# PROC010B_CAN_Interface.net
KiCad netlist of a schematic drawn in Altium Designer
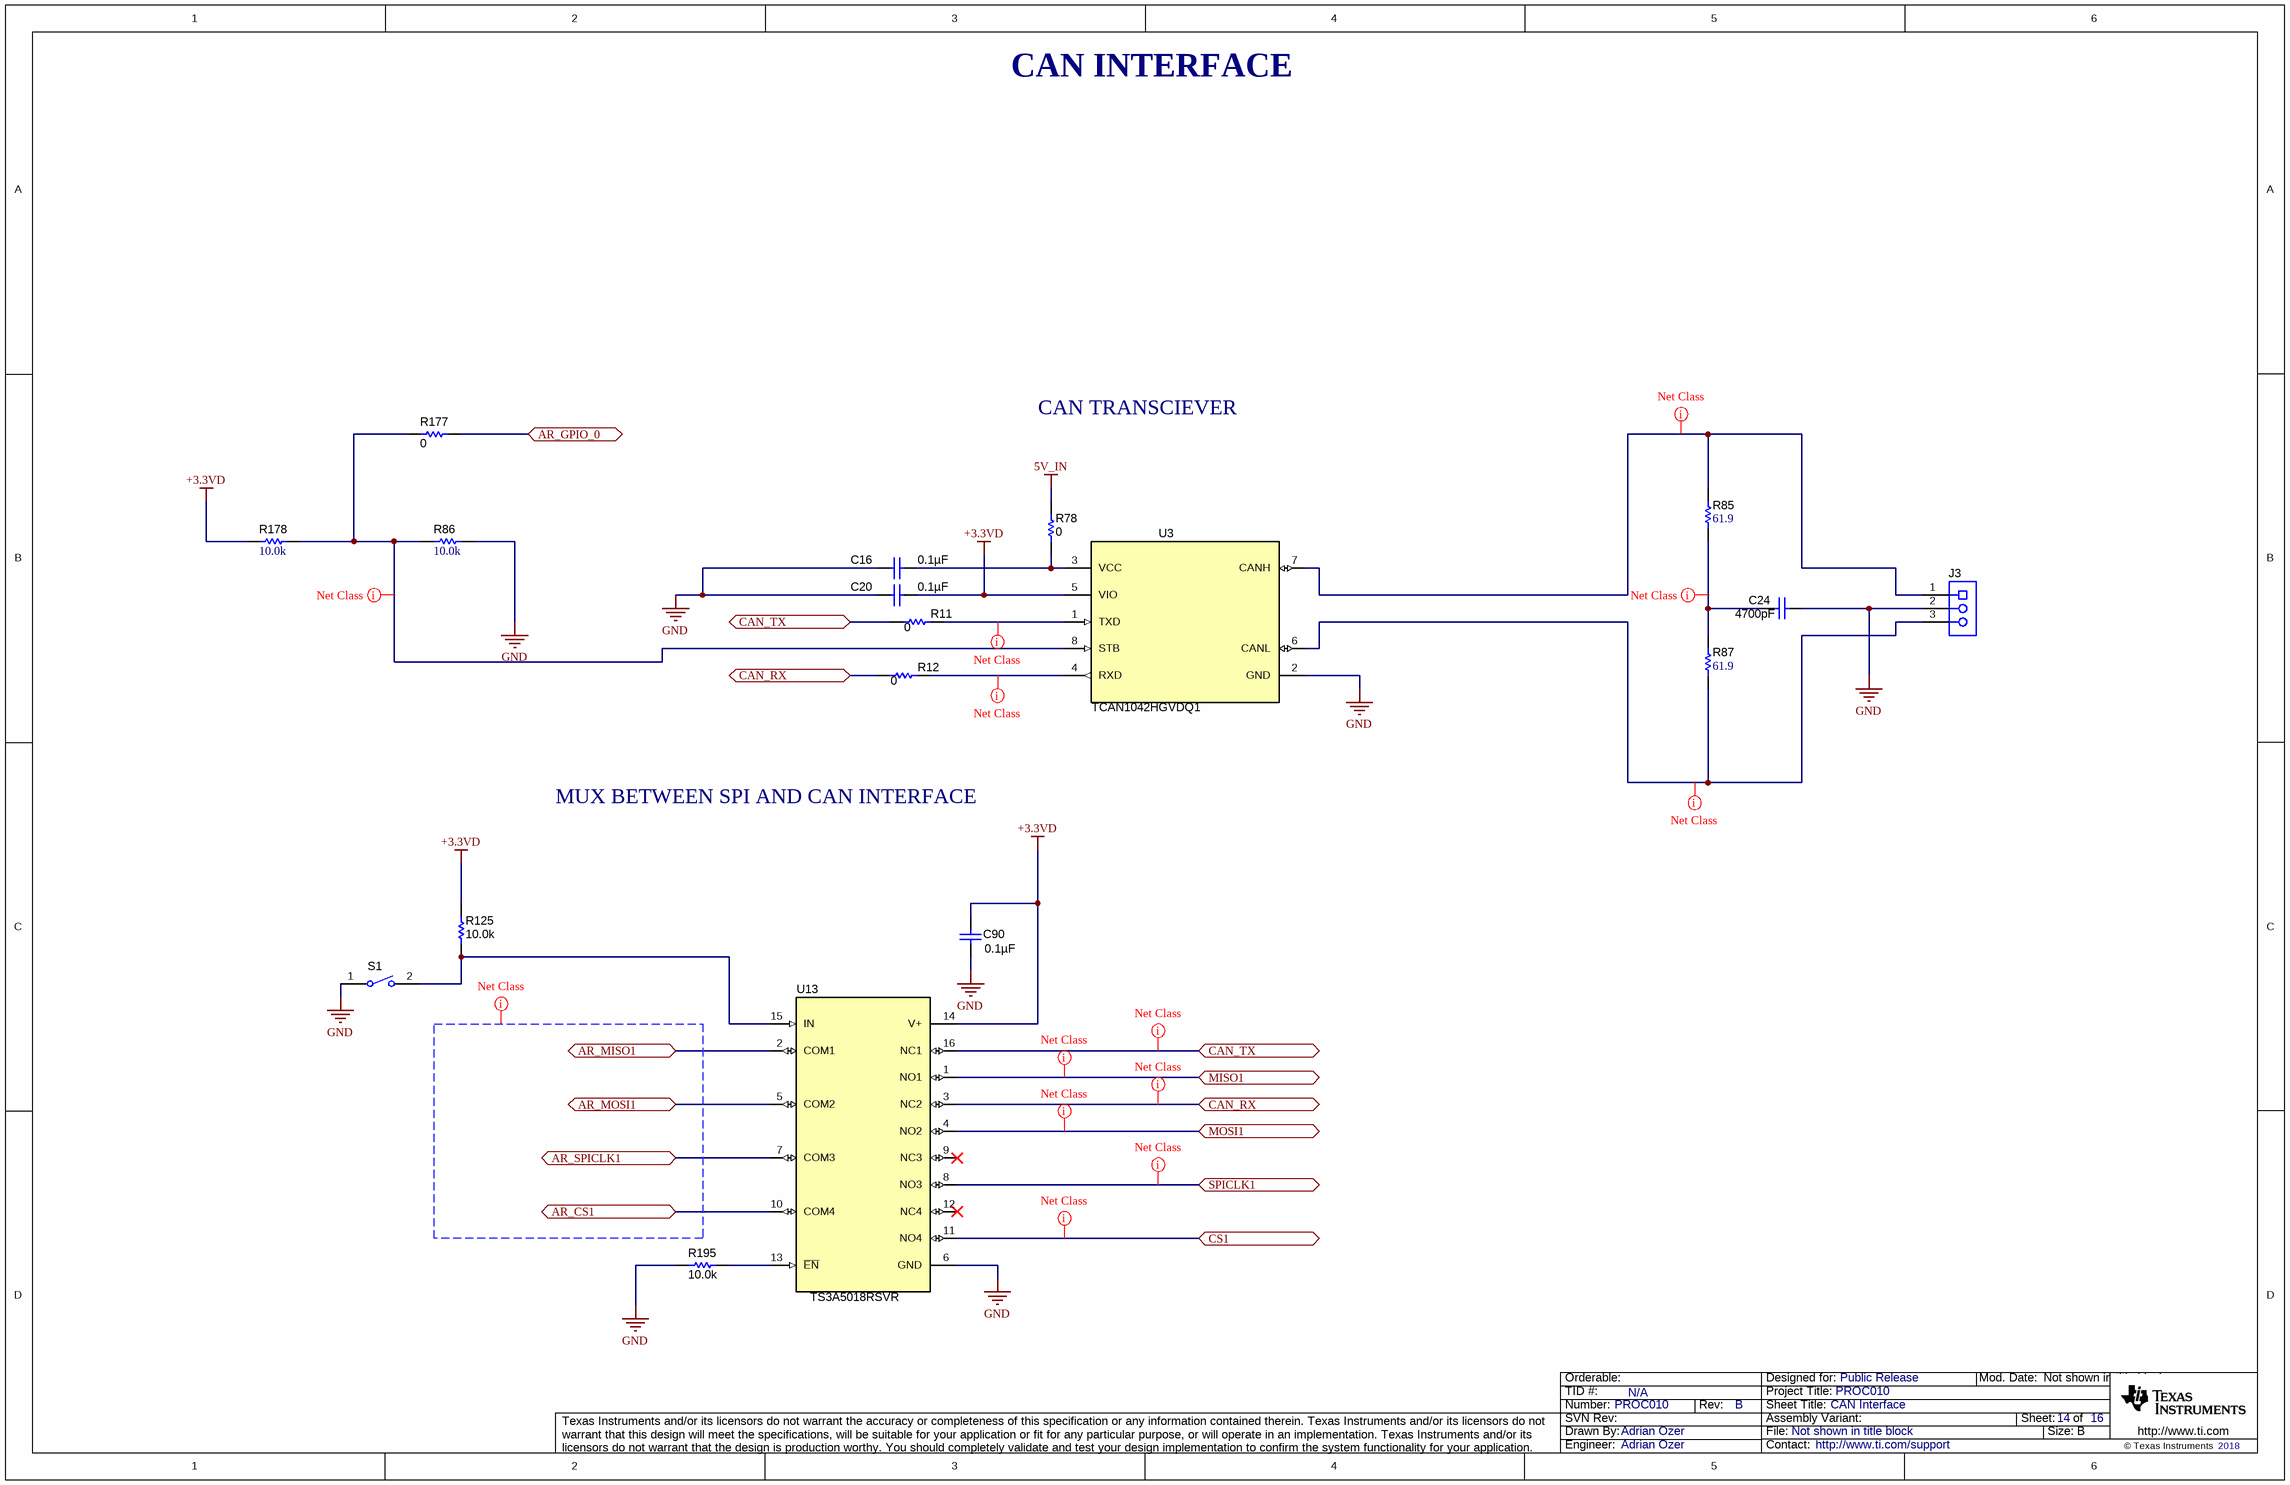
[diagram p0: PROC010B_CAN Interface.SchDoc]

(export (version "E")
  (design (tool "Eeschema 10.0.6"))
  (components
    (comp (ref "C16")
      (value "C0402C104K8RACTU")
      (footprint "0402L")
      (description "CAP, CERM, 0.1 µF, 10 V,+/- 10%, X7R, 0402")
      (fields (field (name "MANUFACTURER") "Kemet") (field (name "VALUEDISPLAYED") "0.1µF"))
      (libsource (lib "Altium Vault - TI") (part "Capacitor"))
    )
    (comp (ref "C20")
      (value "C0402C104K8RACTU")
      (footprint "0402L")
      (description "CAP, CERM, 0.1 µF, 10 V,+/- 10%, X7R, 0402")
      (fields (field (name "MANUFACTURER") "Kemet") (field (name "VALUEDISPLAYED") "0.1µF"))
      (libsource (lib "Altium Vault - TI") (part "Capacitor"))
    )
    (comp (ref "C24")
      (value "C1005X7R1H472K050BA")
      (footprint "0402L")
      (description "CAP, CERM, 4700 pF, 50 V,+/- 10%, X7R, 0402")
      (fields (field (name "MANUFACTURER") "TDK") (field (name "VALUEDISPLAYED") "4700pF"))
      (libsource (lib "Altium Vault - TI") (part "Capacitor"))
    )
    (comp (ref "C90")
      (value "C0402C104K8RACTU")
      (footprint "0402L")
      (description "CAP, CERM, 0.1 µF, 10 V,+/- 10%, X7R, 0402")
      (fields (field (name "MANUFACTURER") "Kemet") (field (name "VALUEDISPLAYED") "0.1µF"))
      (libsource (lib "Altium Vault - TI") (part "Capacitor"))
    )
    (comp (ref "J3")
      (value "OSTTE030161")
      (footprint "On-Shore_OSTTE030161")
      (description "Terminal Block, 3.5mm, 3x1, Tin, R/A, TH")
      (fields
        (field (name "MANUFACTURER") "On-Shore Technology")
        (field (name "PUBLISHER") "Texas Instruments")
      )
      (libsource (lib "Altium Vault - TI") (part "Receptacle_3x1"))
    )
    (comp (ref "R11")
      (value "ERJ-2GE0R00X")
      (footprint "0402L")
      (description "RES, 0, 5%, 0.063 W, 0402")
      (fields
        (field (name "MANUFACTURER") "Panasonic")
        (field (name "VALUEDISPLAYED") "0")
        (field (name "PUBLISHER") "Texas Instruments")
      )
      (libsource (lib "Altium Vault - TI") (part "CMP-0026992-2"))
    )
    (comp (ref "R12")
      (value "ERJ-2GE0R00X")
      (footprint "0402L")
      (description "RES, 0, 5%, 0.063 W, 0402")
      (fields
        (field (name "MANUFACTURER") "Panasonic")
        (field (name "VALUEDISPLAYED") "0")
        (field (name "PUBLISHER") "Texas Instruments")
      )
      (libsource (lib "Altium Vault - TI") (part "CMP-0026992-2"))
    )
    (comp (ref "R78")
      (value "ERJ-2GE0R00X")
      (footprint "0402L")
      (description "RES, 0, 5%, 0.063 W, 0402")
      (fields
        (field (name "MANUFACTURER") "Panasonic")
        (field (name "VALUEDISPLAYED") "0")
        (field (name "PUBLISHER") "Texas Instruments")
      )
      (libsource (lib "Altium Vault - TI") (part "CMP-0026992-2"))
    )
    (comp (ref "R85")
      (value "CRCW040261R9FKED")
      (footprint "0402L")
      (description "RES, 61.9, 1%, 0.063 W, AEC-Q200 Grade 0, 0402")
      (fields (field (name "MANUFACTURER") "Vishay-Dale") (field (name "VALUEDISPLAYED") "61.9"))
      (libsource (lib "Altium Vault - TI") (part "Resistor"))
    )
    (comp (ref "R86")
      (value "CRCW040210K0FKED")
      (footprint "0402L")
      (description "RES, 10.0 k, 1%, 0.063 W, AEC-Q200 Grade 0, 0402")
      (fields (field (name "MANUFACTURER") "Vishay-Dale") (field (name "VALUEDISPLAYED") "10.0k"))
      (libsource (lib "Altium Vault - TI") (part "Resistor"))
    )
    (comp (ref "R87")
      (value "CRCW040261R9FKED")
      (footprint "0402L")
      (description "RES, 61.9, 1%, 0.063 W, AEC-Q200 Grade 0, 0402")
      (fields (field (name "MANUFACTURER") "Vishay-Dale") (field (name "VALUEDISPLAYED") "61.9"))
      (libsource (lib "Altium Vault - TI") (part "Resistor"))
    )
    (comp (ref "R125")
      (value "CRCW040210K0FKED")
      (footprint "0402L")
      (description "RES, 10.0 k, 1%, 0.063 W, 0402")
      (fields
        (field (name "MANUFACTURER") "Vishay-Dale")
        (field (name "VALUEDISPLAYED") "10.0k")
        (field (name "PUBLISHER") "Texas Instruments")
      )
      (libsource (lib "Altium Vault - TI") (part "CMP-0025958-2"))
    )
    (comp (ref "R177")
      (value "ERJ-2GE0R00X")
      (footprint "0402L")
      (description "RES, 0, 5%, 0.063 W, 0402")
      (fields
        (field (name "MANUFACTURER") "Panasonic")
        (field (name "VALUEDISPLAYED") "0")
        (field (name "PUBLISHER") "Texas Instruments")
      )
      (libsource (lib "Altium Vault - TI") (part "CMP-0026992-2"))
    )
    (comp (ref "R178")
      (value "CRCW040210K0FKED")
      (footprint "0402L")
      (description "RES, 10.0 k, 1%, 0.063 W, AEC-Q200 Grade 0, 0402")
      (fields (field (name "MANUFACTURER") "Vishay-Dale") (field (name "VALUEDISPLAYED") "10.0k"))
      (libsource (lib "Altium Vault - TI") (part "Resistor"))
    )
    (comp (ref "R195")
      (value "CRCW040210K0FKED")
      (footprint "0402L")
      (description "RES, 10.0 k, 1%, 0.063 W, 0402")
      (fields
        (field (name "MANUFACTURER") "Vishay-Dale")
        (field (name "VALUEDISPLAYED") "10.0k")
        (field (name "PUBLISHER") "Texas Instruments")
      )
      (libsource (lib "Altium Vault - TI") (part "CMP-0025958-2"))
    )
    (comp (ref "S1")
      (value "CHS-01TB")
      (footprint "SW_CHS-01TB")
      (description "Switch, Slide, SPST, Top Slide, SMT")
      (fields
        (field (name "MANUFACTURER") "Copal Electronics")
        (field (name "PUBLISHER") "Texas Instruments")
      )
      (libsource (lib "Altium Vault - TI") (part "SW_SPST-single"))
    )
    (comp (ref "U3")
      (value "TCAN1042HGVDQ1")
      (footprint "D0008A_L")
      (description "Automotive Fault Protected CAN Transceiver With Flexible Data-Rate, D0008A (SOIC-8)")
      (fields
        (field (name "PARTNUMBER") "TCAN1042HGVDQ1")
        (field (name "MANUFACTURER") "Texas Instruments")
        (field (name "ALTERNATE PARTNUMBER") "TCAN1042HGVDRQ1")
        (field (name "PUBLISHER") "Texas Instruments")
      )
      (libsource (lib "Altium Vault - TI") (part "TCAN1042_V"))
    )
    (comp (ref "U13")
      (value "TS3A5018RSVR")
      (footprint "RSV0016A")
      (description "10-Ohm Quad SPDT Analog Switch, RSV0016A (UQFN-16)")
      (fields
        (field (name "MANUFACTURER") "Texas Instruments")
        (field (name "PARTNUMBER") "TS3A5018RSVR")
        (field (name "PUBLISHER") "Texas Instruments")
      )
      (libsource (lib "Altium Vault - TI") (part "CMP-0067415-1"))
    )
  )
  (nets
    (net (code "1") (name "+3.3VD") (class "Default")
      (node (ref "C20") (pin "2") (pinfunction "2_2") (pintype "passive"))
      (node (ref "C90") (pin "2") (pinfunction "2_2") (pintype "passive"))
      (node (ref "R125") (pin "2") (pinfunction "2_2") (pintype "passive"))
      (node (ref "R178") (pin "1") (pinfunction "1_1") (pintype "passive"))
      (node (ref "U13") (pin "14") (pinfunction "V+_14") (pintype "power_in"))
      (node (ref "U3") (pin "5") (pinfunction "VIO_5") (pintype "power_in"))
    )
    (net (code "2") (name "/AR_CS1") (class "Default")
      (node (ref "U13") (pin "10") (pinfunction "COM4_10") (pintype "bidirectional"))
    )
    (net (code "3") (name "/AR_GPIO_0") (class "Default")
      (node (ref "R177") (pin "2") (pinfunction "2_2") (pintype "passive"))
    )
    (net (code "4") (name "/AR_MISO1") (class "Default")
      (node (ref "U13") (pin "2") (pinfunction "COM1_2") (pintype "bidirectional"))
    )
    (net (code "5") (name "/AR_MOSI1") (class "Default")
      (node (ref "U13") (pin "5") (pinfunction "COM2_5") (pintype "bidirectional"))
    )
    (net (code "6") (name "/AR_SPICLK1") (class "Default")
      (node (ref "U13") (pin "7") (pinfunction "COM3_7") (pintype "bidirectional"))
    )
    (net (code "7") (name "/CAN_RX") (class "Default")
      (node (ref "R12") (pin "1") (pinfunction "1_1") (pintype "passive"))
      (node (ref "U13") (pin "3") (pinfunction "NC2_3") (pintype "bidirectional"))
    )
    (net (code "8") (name "/CAN_TX") (class "Default")
      (node (ref "R11") (pin "1") (pinfunction "1_1") (pintype "passive"))
      (node (ref "U13") (pin "16") (pinfunction "NC1_16") (pintype "bidirectional"))
    )
    (net (code "9") (name "/CS1") (class "Default")
      (node (ref "U13") (pin "11") (pinfunction "NO4_11") (pintype "bidirectional"))
    )
    (net (code "10") (name "/MISO1") (class "Default")
      (node (ref "U13") (pin "1") (pinfunction "NO1_1") (pintype "bidirectional"))
    )
    (net (code "11") (name "/MOSI1") (class "Default")
      (node (ref "U13") (pin "4") (pinfunction "NO2_4") (pintype "bidirectional"))
    )
    (net (code "12") (name "/SPICLK1") (class "Default")
      (node (ref "U13") (pin "8") (pinfunction "NO3_8") (pintype "bidirectional"))
    )
    (net (code "13") (name "5V_IN") (class "Default")
      (node (ref "R78") (pin "2") (pinfunction "2_2") (pintype "passive"))
    )
    (net (code "14") (name "GND") (class "Default")
      (node (ref "C16") (pin "1") (pinfunction "1_1") (pintype "passive"))
      (node (ref "C20") (pin "1") (pinfunction "1_1") (pintype "passive"))
      (node (ref "C24") (pin "1") (pinfunction "1_1") (pintype "passive"))
      (node (ref "C90") (pin "1") (pinfunction "1_1") (pintype "passive"))
      (node (ref "J3") (pin "2") (pinfunction "2_2") (pintype "passive"))
      (node (ref "R195") (pin "2") (pinfunction "2_2") (pintype "passive"))
      (node (ref "R86") (pin "2") (pinfunction "2_2") (pintype "passive"))
      (node (ref "S1") (pin "1") (pinfunction "1_1") (pintype "passive"))
      (node (ref "U13") (pin "6") (pinfunction "GND_6") (pintype "power_in"))
      (node (ref "U3") (pin "2") (pinfunction "GND_2") (pintype "power_in"))
    )
    (net (code "15") (name "Net-(C24-Pad2)") (class "Default")
      (node (ref "C24") (pin "2") (pinfunction "2_2") (pintype "passive"))
      (node (ref "R85") (pin "1") (pinfunction "1_1") (pintype "passive"))
      (node (ref "R87") (pin "2") (pinfunction "2_2") (pintype "passive"))
    )
    (net (code "16") (name "Net-(U3-CANH)") (class "Default")
      (node (ref "J3") (pin "1") (pinfunction "1_1") (pintype "passive"))
      (node (ref "R85") (pin "2") (pinfunction "2_2") (pintype "passive"))
      (node (ref "U3") (pin "7") (pinfunction "CANH_7") (pintype "bidirectional"))
    )
    (net (code "17") (name "Net-(U3-CANL)") (class "Default")
      (node (ref "J3") (pin "3") (pinfunction "3_3") (pintype "passive"))
      (node (ref "R87") (pin "1") (pinfunction "1_1") (pintype "passive"))
      (node (ref "U3") (pin "6") (pinfunction "CANL_6") (pintype "bidirectional"))
    )
    (net (code "18") (name "Net-(U3-RXD)") (class "Default")
      (node (ref "R12") (pin "2") (pinfunction "2_2") (pintype "passive"))
      (node (ref "U3") (pin "4") (pinfunction "RXD_4") (pintype "output"))
    )
    (net (code "19") (name "Net-(U3-STB)") (class "Default")
      (node (ref "R177") (pin "1") (pinfunction "1_1") (pintype "passive"))
      (node (ref "R178") (pin "2") (pinfunction "2_2") (pintype "passive"))
      (node (ref "R86") (pin "1") (pinfunction "1_1") (pintype "passive"))
      (node (ref "U3") (pin "8") (pinfunction "STB_8") (pintype "input"))
    )
    (net (code "20") (name "Net-(U3-TXD)") (class "Default")
      (node (ref "R11") (pin "2") (pinfunction "2_2") (pintype "passive"))
      (node (ref "U3") (pin "1") (pinfunction "TXD_1") (pintype "input"))
    )
    (net (code "21") (name "Net-(U3-VCC)") (class "Default")
      (node (ref "C16") (pin "2") (pinfunction "2_2") (pintype "passive"))
      (node (ref "R78") (pin "1") (pinfunction "1_1") (pintype "passive"))
      (node (ref "U3") (pin "3") (pinfunction "VCC_3") (pintype "power_in"))
    )
    (net (code "22") (name "Net-(U13-EN)") (class "Default")
      (node (ref "R195") (pin "1") (pinfunction "1_1") (pintype "passive"))
      (node (ref "U13") (pin "13") (pinfunction "EN_13") (pintype "input"))
    )
    (net (code "23") (name "Net-(U13-IN)") (class "Default")
      (node (ref "R125") (pin "1") (pinfunction "1_1") (pintype "passive"))
      (node (ref "S1") (pin "2") (pinfunction "2_2") (pintype "passive"))
      (node (ref "U13") (pin "15") (pinfunction "IN_15") (pintype "input"))
    )
    (net (code "24") (name "unconnected-(U13-NC3-Pad9)") (class "Default")
      (node (ref "U13") (pin "9") (pinfunction "NC3_9") (pintype "bidirectional+no_connect"))
    )
    (net (code "25") (name "unconnected-(U13-NC4-Pad12)") (class "Default")
      (node (ref "U13") (pin "12") (pinfunction "NC4_12") (pintype "bidirectional+no_connect"))
    )
  )
)
